# USB_Host.net
KiCad netlist of a schematic drawn in Altium Designer
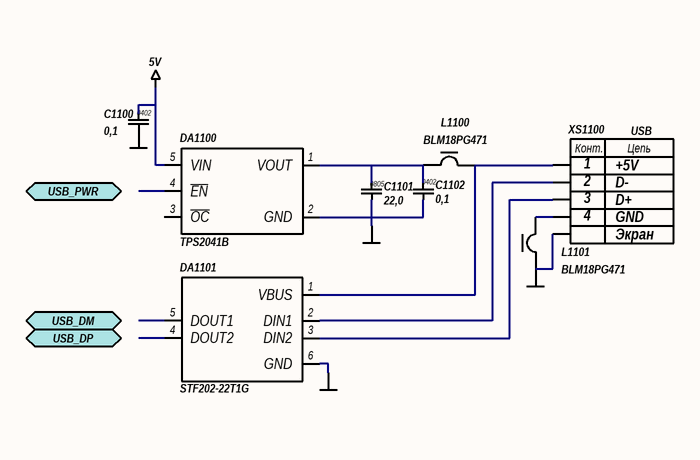
[diagram p0: USB Host.SchDoc]

(export (version "E")
  (design (tool "Eeschema 10.0.6"))
  (components
    (comp (ref "C1100")
      (value "0,1")
      (footprint "CAP0402")
      (description "Конденсатор чип")
      (libsource (lib "EwgPassive") (part "CAP_0402"))
    )
    (comp (ref "C1101")
      (value "22,0")
      (footprint "CAP0805")
      (description "Конденсатор чип")
      (libsource (lib "EwgPassive") (part "CAP_0805"))
    )
    (comp (ref "C1102")
      (value "0,1")
      (footprint "CAP0402")
      (description "Конденсатор чип")
      (libsource (lib "EwgPassive") (part "CAP_0402"))
    )
    (comp (ref "DA1100")
      (value "TPS2041B")
      (footprint "SOT23-5")
      (description "Интерфейс USB контроллер питания")
      (libsource (lib "EwgMicrochips") (part "TPS2041B"))
    )
    (comp (ref "DA1101")
      (value "STF202-22T1G")
      (footprint "SOT23-6")
      (description "Интерфейс USB защита+фильтр")
      (libsource (lib "EwgMicrochips") (part "STF202-22T1G"))
    )
    (comp (ref "L1100")
      (value "BLM18PG471")
      (footprint "FB0603")
      (description "Ферритовая бусина")
      (libsource (lib "EwgPassive") (part "BLM18PG"))
    )
    (comp (ref "L1101")
      (value "BLM18PG471")
      (footprint "FB0603")
      (description "Ферритовая бусина")
      (libsource (lib "EwgPassive") (part "BLM18PG"))
    )
    (comp (ref "XS1100")
      (value "USB")
      (footprint "USB-A 1J")
      (description "Разъем USB")
      (libsource (lib "EwgConnectors") (part "USB 1J"))
    )
  )
  (nets
    (net (code "4") (name "5V") (class "Default")
      (node (ref "C1100") (pin "1") (pintype "passive"))
      (node (ref "DA1100") (pin "5") (pinfunction "VIN_5") (pintype "passive"))
    )
    (net (code "5") (name "GND") (class "Default")
      (node (ref "C1100") (pin "2") (pintype "passive"))
      (node (ref "C1101") (pin "2") (pintype "passive"))
      (node (ref "C1102") (pin "2") (pintype "passive"))
      (node (ref "DA1100") (pin "2") (pinfunction "GND_2") (pintype "passive"))
      (node (ref "DA1101") (pin "6") (pinfunction "GND_6") (pintype "passive"))
      (node (ref "L1101") (pin "1") (pintype "passive"))
      (node (ref "XS1100") (pin "0") (pinfunction "Экран_0") (pintype "passive"))
    )
    (net (code "6") (name "Net-(DA1100-VOUT)") (class "Default")
      (node (ref "C1101") (pin "1") (pintype "passive"))
      (node (ref "C1102") (pin "1") (pintype "passive"))
      (node (ref "DA1100") (pin "1") (pinfunction "VOUT_1") (pintype "passive"))
      (node (ref "L1100") (pin "1") (pintype "passive"))
    )
    (net (code "7") (name "Net-(DA1101-DIN1)") (class "Default")
      (node (ref "DA1101") (pin "2") (pinfunction "DIN1_2") (pintype "passive"))
      (node (ref "XS1100") (pin "2") (pinfunction "D-_2") (pintype "passive"))
    )
    (net (code "8") (name "Net-(DA1101-DIN2)") (class "Default")
      (node (ref "DA1101") (pin "3") (pinfunction "DIN2_3") (pintype "passive"))
      (node (ref "XS1100") (pin "3") (pinfunction "D+_3") (pintype "passive"))
    )
    (net (code "9") (name "Net-(DA1101-VBUS)") (class "Default")
      (node (ref "DA1101") (pin "1") (pinfunction "VBUS_1") (pintype "passive"))
      (node (ref "L1100") (pin "2") (pintype "passive"))
      (node (ref "XS1100") (pin "1") (pinfunction "+5V_1") (pintype "passive"))
    )
    (net (code "10") (name "Net-(XS1100-GND)") (class "Default")
      (node (ref "L1101") (pin "2") (pintype "passive"))
      (node (ref "XS1100") (pin "4") (pinfunction "GND_4") (pintype "passive"))
    )
    (net (code "11") (name "unconnected-(DA1100-~{EN}-Pad4)") (class "Default")
      (node (ref "DA1100") (pin "4") (pinfunction "~{EN}_4") (pintype "passive"))
    )
    (net (code "12") (name "unconnected-(DA1100-~{OC}-Pad3)") (class "Default")
      (node (ref "DA1100") (pin "3") (pinfunction "~{OC}_3") (pintype "passive"))
    )
    (net (code "13") (name "unconnected-(DA1101-DOUT1-Pad5)") (class "Default")
      (node (ref "DA1101") (pin "5") (pinfunction "DOUT1_5") (pintype "passive"))
    )
    (net (code "14") (name "unconnected-(DA1101-DOUT2-Pad4)") (class "Default")
      (node (ref "DA1101") (pin "4") (pinfunction "DOUT2_4") (pintype "passive"))
    )
  )
)
